# TopLevel.net
KiCad netlist of a schematic drawn in Altium Designer
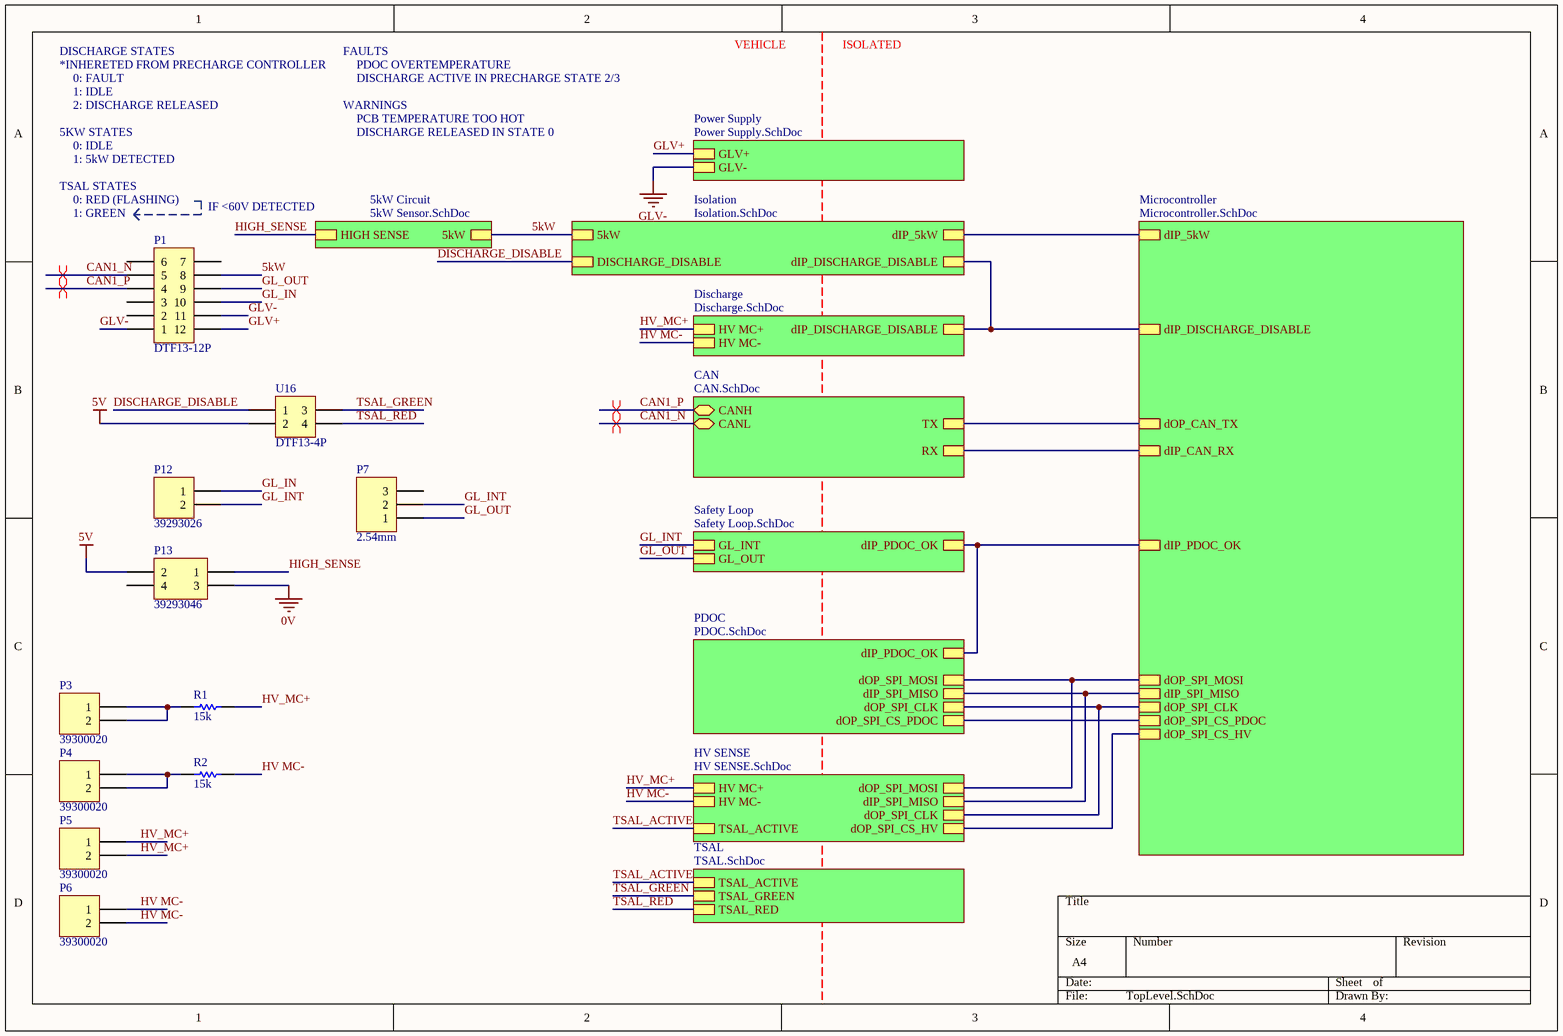
[diagram p0: TopLevel.SchDoc]

(export (version "E")
  (design (tool "Eeschema 10.0.6"))
  (components
    (comp (ref "P1")
      (value "DTF13-12P")
      (footprint "DTF13-12P")
      (fields (field (name "DIGIKEY PART NUMBER") "1734-1861-ND") (field (name "CONTACT") "Copper Alloy"))
      (libsource (lib "ts_standard_connectors") (part "DT13-12P"))
    )
    (comp (ref "P3")
      (value "39300020")
      (footprint "39300020")
      (fields (field (name "DIGIKEY PART NUMBER") "WM21351-ND") (field (name "CONTACT") "Tin"))
      (libsource (lib "ts_standard_connectors") (part "2"))
    )
    (comp (ref "P4")
      (value "39300020")
      (footprint "39300020")
      (fields (field (name "DIGIKEY PART NUMBER") "WM21351-ND") (field (name "CONTACT") "Tin"))
      (libsource (lib "ts_standard_connectors") (part "2"))
    )
    (comp (ref "P5")
      (value "39300020")
      (footprint "39300020")
      (fields (field (name "DIGIKEY PART NUMBER") "WM21351-ND") (field (name "CONTACT") "Tin"))
      (libsource (lib "ts_standard_connectors") (part "2"))
    )
    (comp (ref "P6")
      (value "39300020")
      (footprint "39300020")
      (fields (field (name "DIGIKEY PART NUMBER") "WM21351-ND") (field (name "CONTACT") "Tin"))
      (libsource (lib "ts_standard_connectors") (part "2"))
    )
    (comp (ref "P7")
      (value "2.54mm")
      (footprint "TH 2.54mm Header 1x3")
      (fields (field (name "PART NUMBER") "TH 2.54mm Header 1x3") (field (name "CONTACT") "NA"))
      (libsource (lib "ts_standard_connectors") (part "Header 1x3"))
    )
    (comp (ref "P12")
      (value "39293026")
      (footprint "39293026")
      (fields (field (name "DIGIKEY PART NUMBER") "WM3843-ND") (field (name "CONTACT") "Tin"))
      (libsource (lib "ts_standard_connectors") (part "2"))
    )
    (comp (ref "P13")
      (value "39293046")
      (footprint "39293046")
      (fields (field (name "DIGIKEY PART NUMBER") "WM3844-ND") (field (name "CONTACT") "Tin"))
      (libsource (lib "ts_standard_connectors") (part "4"))
    )
    (comp (ref "R1")
      (value "15k")
      (footprint "TE_SMF7")
      (fields
        (field (name "PART NUMBER") "SMF715KJ")
        (field (name "MANUFACTURER") "TE")
        (field (name "TOLERANCE") "0.05")
      )
      (libsource (lib "ts_standard_library") (part "Resistor"))
    )
    (comp (ref "R2")
      (value "15k")
      (footprint "TE_SMF7")
      (fields
        (field (name "PART NUMBER") "SMF715KJ")
        (field (name "MANUFACTURER") "TE")
        (field (name "TOLERANCE") "0.05")
      )
      (libsource (lib "ts_standard_library") (part "Resistor"))
    )
    (comp (ref "U16")
      (value "DTF13-4P")
      (footprint "DTF13-4P")
      (fields (field (name "DIGIKEY PART NUMBER") "1734-1646-ND") (field (name "CONTACT") "Copper Alloy"))
      (libsource (lib "ts_standard_connectors") (part "DT13-4P"))
    )
  )
  (nets
    (net (code "1") (name "/5kW") (class "Default")
      (node (ref "P1") (pin "8") (pinfunction "8_8") (pintype "passive"))
    )
    (net (code "2") (name "/CAN1_N") (class "Default")
      (node (ref "P1") (pin "5") (pinfunction "5_5") (pintype "power_in"))
    )
    (net (code "3") (name "/CAN1_P") (class "Default")
      (node (ref "P1") (pin "4") (pinfunction "4_4") (pintype "power_in"))
    )
    (net (code "4") (name "/DISCHARGE_DISABLE") (class "Default")
      (node (ref "U16") (pin "1") (pinfunction "1_1") (pintype "power_in"))
    )
    (net (code "5") (name "/GLV+") (class "Default")
      (node (ref "P1") (pin "12") (pinfunction "12_12") (pintype "passive"))
    )
    (net (code "6") (name "/GL_IN") (class "Default")
      (node (ref "P1") (pin "10") (pinfunction "10_10") (pintype "passive"))
      (node (ref "P12") (pin "1") (pinfunction "1_1") (pintype "passive"))
    )
    (net (code "7") (name "/GL_INT") (class "Default")
      (node (ref "P12") (pin "2") (pinfunction "2_2") (pintype "passive"))
      (node (ref "P7") (pin "2") (pinfunction "2_2") (pintype "passive"))
    )
    (net (code "8") (name "/GL_OUT") (class "Default")
      (node (ref "P1") (pin "9") (pinfunction "9_9") (pintype "passive"))
      (node (ref "P7") (pin "1") (pinfunction "1_1") (pintype "passive"))
    )
    (net (code "9") (name "/HIGH_SENSE") (class "Default")
      (node (ref "P13") (pin "1") (pinfunction "1_1") (pintype "passive"))
    )
    (net (code "10") (name "/HV MC-") (class "Default")
      (node (ref "P6") (pin "1") (pinfunction "1_1") (pintype "passive"))
      (node (ref "P6") (pin "2") (pinfunction "2_2") (pintype "passive"))
      (node (ref "R2") (pin "2") (pinfunction "2_2") (pintype "passive"))
    )
    (net (code "11") (name "/HV_MC+") (class "Default")
      (node (ref "P5") (pin "1") (pinfunction "1_1") (pintype "passive"))
      (node (ref "P5") (pin "2") (pinfunction "2_2") (pintype "passive"))
      (node (ref "R1") (pin "2") (pinfunction "2_2") (pintype "passive"))
    )
    (net (code "14") (name "/TSAL_GREEN") (class "Default")
      (node (ref "U16") (pin "3") (pinfunction "3_3") (pintype "passive"))
    )
    (net (code "15") (name "/TSAL_RED") (class "Default")
      (node (ref "U16") (pin "4") (pinfunction "4_4") (pintype "passive"))
    )
    (net (code "25") (name "0V") (class "Default")
      (node (ref "P13") (pin "3") (pinfunction "3_3") (pintype "passive"))
    )
    (net (code "26") (name "5V") (class "Default")
      (node (ref "P13") (pin "2") (pinfunction "2_2") (pintype "passive"))
      (node (ref "U16") (pin "2") (pinfunction "2_2") (pintype "power_in"))
    )
    (net (code "27") (name "GLV-") (class "Default")
      (node (ref "P1") (pin "1") (pinfunction "1_1") (pintype "power_in"))
      (node (ref "P1") (pin "11") (pinfunction "11_11") (pintype "passive"))
    )
    (net (code "28") (name "Net-(P3-Pad1)") (class "Default")
      (node (ref "P3") (pin "1") (pinfunction "1_1") (pintype "passive"))
      (node (ref "P3") (pin "2") (pinfunction "2_2") (pintype "passive"))
      (node (ref "R1") (pin "1") (pinfunction "1_1") (pintype "passive"))
    )
    (net (code "29") (name "Net-(P4-Pad1)") (class "Default")
      (node (ref "P4") (pin "1") (pinfunction "1_1") (pintype "passive"))
      (node (ref "P4") (pin "2") (pinfunction "2_2") (pintype "passive"))
      (node (ref "R2") (pin "1") (pinfunction "1_1") (pintype "passive"))
    )
    (net (code "30") (name "unconnected-(P1-Pad2)") (class "Default")
      (node (ref "P1") (pin "2") (pinfunction "2_2") (pintype "power_in"))
    )
    (net (code "31") (name "unconnected-(P1-Pad3)") (class "Default")
      (node (ref "P1") (pin "3") (pinfunction "3_3") (pintype "power_in"))
    )
    (net (code "32") (name "unconnected-(P1-Pad6)") (class "Default")
      (node (ref "P1") (pin "6") (pinfunction "6_6") (pintype "power_in"))
    )
    (net (code "33") (name "unconnected-(P1-Pad7)") (class "Default")
      (node (ref "P1") (pin "7") (pinfunction "7_7") (pintype "passive"))
    )
    (net (code "34") (name "unconnected-(P7-Pad3)") (class "Default")
      (node (ref "P7") (pin "3") (pinfunction "3_3") (pintype "passive"))
    )
    (net (code "35") (name "unconnected-(P13-Pad4)") (class "Default")
      (node (ref "P13") (pin "4") (pinfunction "4_4") (pintype "passive"))
    )
  )
)
